# AlimentationLabo-Debutant.net
KiCad netlist of a schematic drawn in EAGLE
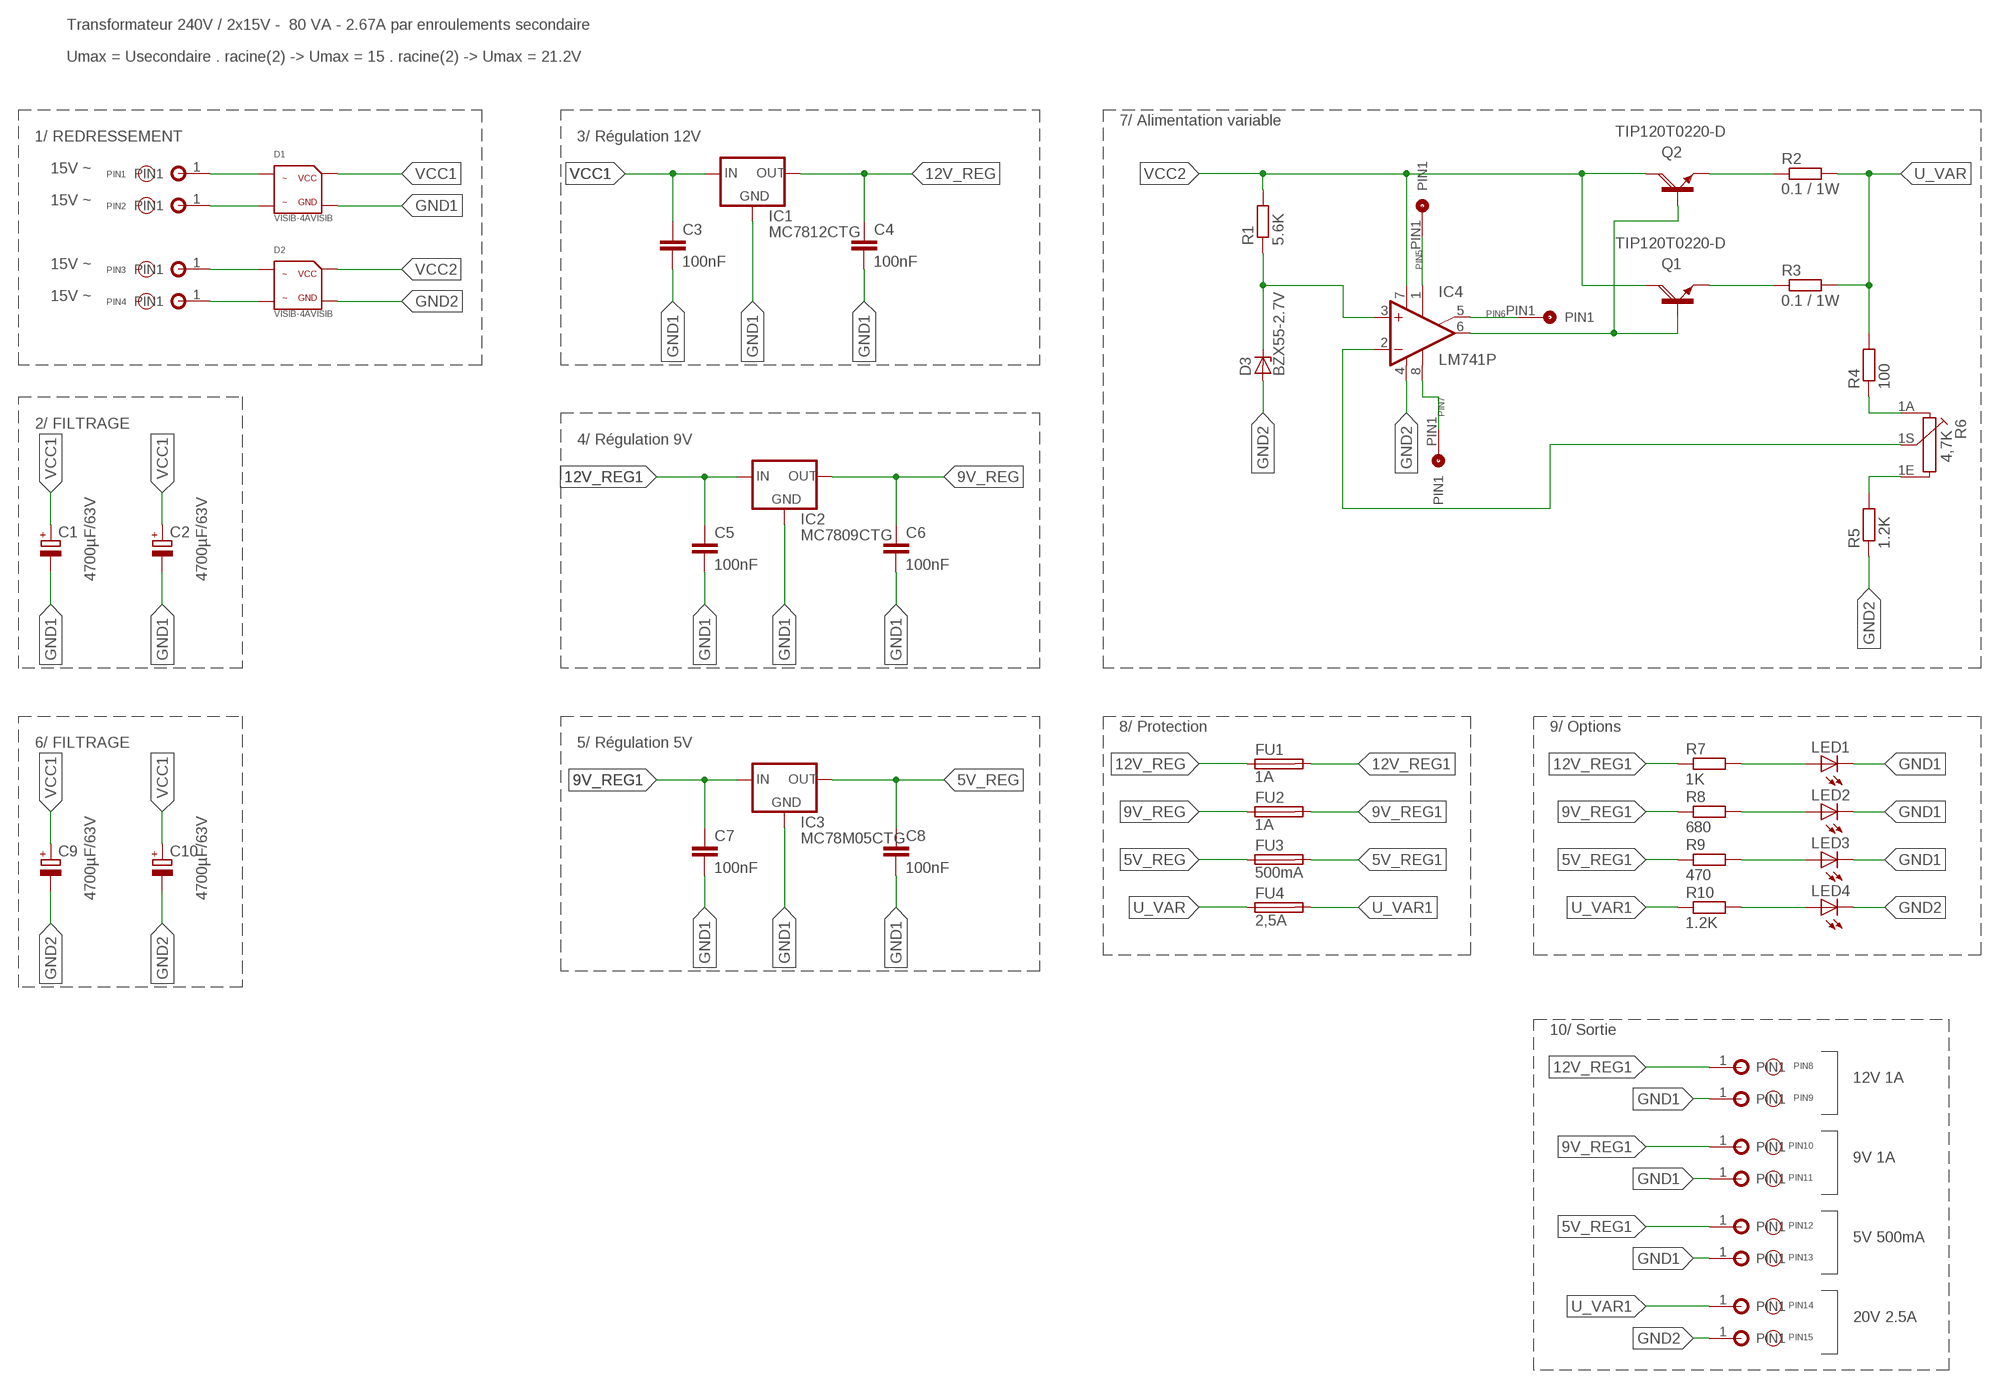
[diagram p0: schematic, sheet 1]

(export (version "E")
  (design (tool "Eeschema 10.0.6"))
  (components
    (comp (ref "C1")
      (value "4700µF/63V")
      (footprint "eagle-import:EB25D")
      (libsource (lib "eagle-import") (part "CPOL-EUE10-25"))
    )
    (comp (ref "C2")
      (value "4700µF/63V")
      (footprint "eagle-import:EB25D")
      (libsource (lib "eagle-import") (part "CPOL-EUE10-25"))
    )
    (comp (ref "C3")
      (value "100nF")
      (footprint "eagle-import:C0805")
      (libsource (lib "eagle-import") (part "C-EUC0805"))
    )
    (comp (ref "C4")
      (value "100nF")
      (footprint "eagle-import:C0805")
      (libsource (lib "eagle-import") (part "C-EUC0805"))
    )
    (comp (ref "C5")
      (value "100nF")
      (footprint "eagle-import:C0805")
      (libsource (lib "eagle-import") (part "C-EUC0805"))
    )
    (comp (ref "C6")
      (value "100nF")
      (footprint "eagle-import:C0805")
      (libsource (lib "eagle-import") (part "C-EUC0805"))
    )
    (comp (ref "C7")
      (value "100nF")
      (footprint "eagle-import:C0805")
      (libsource (lib "eagle-import") (part "C-EUC0805"))
    )
    (comp (ref "C8")
      (value "100nF")
      (footprint "eagle-import:C0805")
      (libsource (lib "eagle-import") (part "C-EUC0805"))
    )
    (comp (ref "C9")
      (value "4700µF/63V")
      (footprint "eagle-import:EB25D")
      (libsource (lib "eagle-import") (part "CPOL-EUE10-25"))
    )
    (comp (ref "C10")
      (value "4700µF/63V")
      (footprint "eagle-import:EB25D")
      (libsource (lib "eagle-import") (part "CPOL-EUE10-25"))
    )
    (comp (ref "D1")
      (value "VISIB-4AVISIB")
      (footprint "eagle-import:VISIB-4A")
      (libsource (lib "eagle-import") (part "VISIB-4AVISIB"))
    )
    (comp (ref "D2")
      (value "VISIB-4AVISIB")
      (footprint "eagle-import:VISIB-4A")
      (libsource (lib "eagle-import") (part "VISIB-4AVISIB"))
    )
    (comp (ref "D3")
      (value "BZX55-2.7V")
      (footprint "eagle-import:DO35Z10")
      (libsource (lib "eagle-import") (part "BZX55"))
    )
    (comp (ref "FU1")
      (value "1A")
      (footprint "eagle-import:MC36226")
      (libsource (lib "eagle-import") (part "MC36226SMD1812"))
    )
    (comp (ref "FU2")
      (value "1A")
      (footprint "eagle-import:MC36226")
      (libsource (lib "eagle-import") (part "MC36226SMD1812"))
    )
    (comp (ref "FU3")
      (value "500mA")
      (footprint "eagle-import:MC36226")
      (libsource (lib "eagle-import") (part "MC36226SMD1812"))
    )
    (comp (ref "FU4")
      (value "2,5A")
      (footprint "eagle-import:MC36226")
      (libsource (lib "eagle-import") (part "MC36226SMD1812"))
    )
    (comp (ref "IC1")
      (value "MC7812CTG")
      (footprint "eagle-import:78XXS")
      (libsource (lib "eagle-import") (part "78XXS"))
    )
    (comp (ref "IC2")
      (value "MC7809CTG")
      (footprint "eagle-import:78XXS")
      (libsource (lib "eagle-import") (part "78XXS"))
    )
    (comp (ref "IC3")
      (value "MC78M05CTG")
      (footprint "eagle-import:78XXS")
      (libsource (lib "eagle-import") (part "78XXS"))
    )
    (comp (ref "IC4")
      (value "LM741P")
      (footprint "eagle-import:DIL08")
      (libsource (lib "eagle-import") (part "741PLM"))
    )
    (comp (ref "LED1")
      (value "LED5MM")
      (footprint "eagle-import:LED5MM")
      (libsource (lib "eagle-import") (part "LED5MM"))
    )
    (comp (ref "LED2")
      (value "LED5MM")
      (footprint "eagle-import:LED5MM")
      (libsource (lib "eagle-import") (part "LED5MM"))
    )
    (comp (ref "LED3")
      (value "LED5MM")
      (footprint "eagle-import:LED5MM")
      (libsource (lib "eagle-import") (part "LED5MM"))
    )
    (comp (ref "LED4")
      (value "LED5MM")
      (footprint "eagle-import:LED5MM")
      (libsource (lib "eagle-import") (part "LED5MM"))
    )
    (comp (ref "PIN1")
      (value "CON-FILTRAVERSANT-1PIN")
      (footprint "eagle-import:CON-FILTRAVERSANT-T2")
      (libsource (lib "eagle-import") (part "CON-FILTRAVERSANT-1PIN"))
    )
    (comp (ref "PIN2")
      (value "CON-FILTRAVERSANT-1PIN")
      (footprint "eagle-import:CON-FILTRAVERSANT-T2")
      (libsource (lib "eagle-import") (part "CON-FILTRAVERSANT-1PIN"))
    )
    (comp (ref "PIN3")
      (value "CON-FILTRAVERSANT-1PIN")
      (footprint "eagle-import:CON-FILTRAVERSANT-T2")
      (libsource (lib "eagle-import") (part "CON-FILTRAVERSANT-1PIN"))
    )
    (comp (ref "PIN4")
      (value "CON-FILTRAVERSANT-1PIN")
      (footprint "eagle-import:CON-FILTRAVERSANT-T2")
      (libsource (lib "eagle-import") (part "CON-FILTRAVERSANT-1PIN"))
    )
    (comp (ref "PIN5")
      (value "CON-TRAV-1PIN")
      (footprint "eagle-import:CON-TRAV-1")
      (libsource (lib "eagle-import") (part "CON-TRAV-1PIN"))
    )
    (comp (ref "PIN6")
      (value "CON-TRAV-1PIN")
      (footprint "eagle-import:CON-TRAV-1")
      (libsource (lib "eagle-import") (part "CON-TRAV-1PIN"))
    )
    (comp (ref "PIN7")
      (value "CON-TRAV-1PIN")
      (footprint "eagle-import:CON-TRAV-1")
      (libsource (lib "eagle-import") (part "CON-TRAV-1PIN"))
    )
    (comp (ref "PIN8")
      (value "CON-FILTRAVERSANT-1PIN")
      (footprint "eagle-import:CON-FILTRAVERSANT-T2")
      (libsource (lib "eagle-import") (part "CON-FILTRAVERSANT-1PIN"))
    )
    (comp (ref "PIN9")
      (value "CON-FILTRAVERSANT-1PIN")
      (footprint "eagle-import:CON-FILTRAVERSANT-T2")
      (libsource (lib "eagle-import") (part "CON-FILTRAVERSANT-1PIN"))
    )
    (comp (ref "PIN10")
      (value "CON-FILTRAVERSANT-1PIN")
      (footprint "eagle-import:CON-FILTRAVERSANT-T2")
      (libsource (lib "eagle-import") (part "CON-FILTRAVERSANT-1PIN"))
    )
    (comp (ref "PIN11")
      (value "CON-FILTRAVERSANT-1PIN")
      (footprint "eagle-import:CON-FILTRAVERSANT-T2")
      (libsource (lib "eagle-import") (part "CON-FILTRAVERSANT-1PIN"))
    )
    (comp (ref "PIN12")
      (value "CON-FILTRAVERSANT-1PIN")
      (footprint "eagle-import:CON-FILTRAVERSANT-T2")
      (libsource (lib "eagle-import") (part "CON-FILTRAVERSANT-1PIN"))
    )
    (comp (ref "PIN13")
      (value "CON-FILTRAVERSANT-1PIN")
      (footprint "eagle-import:CON-FILTRAVERSANT-T2")
      (libsource (lib "eagle-import") (part "CON-FILTRAVERSANT-1PIN"))
    )
    (comp (ref "PIN14")
      (value "CON-FILTRAVERSANT-1PIN")
      (footprint "eagle-import:CON-FILTRAVERSANT-T2")
      (libsource (lib "eagle-import") (part "CON-FILTRAVERSANT-1PIN"))
    )
    (comp (ref "PIN15")
      (value "CON-FILTRAVERSANT-1PIN")
      (footprint "eagle-import:CON-FILTRAVERSANT-T2")
      (libsource (lib "eagle-import") (part "CON-FILTRAVERSANT-1PIN"))
    )
    (comp (ref "Q1")
      (value "TIP120T0220-D")
      (footprint "eagle-import:T0220-D")
      (libsource (lib "eagle-import") (part "TIP120T0220-D"))
    )
    (comp (ref "Q2")
      (value "TIP120T0220-D")
      (footprint "eagle-import:T0220-D")
      (libsource (lib "eagle-import") (part "TIP120T0220-D"))
    )
    (comp (ref "R1")
      (value "5.6K")
      (footprint "eagle-import:R0805")
      (libsource (lib "eagle-import") (part "R-EU_R0805"))
    )
    (comp (ref "R2")
      (value "0.1 / 1W")
      (footprint "eagle-import:P0817_22")
      (libsource (lib "eagle-import") (part "R-EU_0817/22"))
    )
    (comp (ref "R3")
      (value "0.1 / 1W")
      (footprint "eagle-import:P0817_22")
      (libsource (lib "eagle-import") (part "R-EU_0817/22"))
    )
    (comp (ref "R4")
      (value "100")
      (footprint "eagle-import:R0805")
      (libsource (lib "eagle-import") (part "R-EU_R0805"))
    )
    (comp (ref "R5")
      (value "1.2K")
      (footprint "eagle-import:R0805")
      (libsource (lib "eagle-import") (part "R-EU_R0805"))
    )
    (comp (ref "R6")
      (value "4,7K")
      (footprint "eagle-import:PC16S")
      (libsource (lib "eagle-import") (part "PC16S"))
    )
    (comp (ref "R7")
      (value "1K")
      (footprint "eagle-import:R0805")
      (libsource (lib "eagle-import") (part "R-EU_R0805"))
    )
    (comp (ref "R8")
      (value "680")
      (footprint "eagle-import:R0805")
      (libsource (lib "eagle-import") (part "R-EU_R0805"))
    )
    (comp (ref "R9")
      (value "470")
      (footprint "eagle-import:R0805")
      (libsource (lib "eagle-import") (part "R-EU_R0805"))
    )
    (comp (ref "R10")
      (value "1.2K")
      (footprint "eagle-import:R0805")
      (libsource (lib "eagle-import") (part "R-EU_R0805"))
    )
  )
  (nets
    (net (code "1") (name "5V_REG") (class "Default")
      (node (ref "C8") (pin "1") (pinfunction "1_1") (pintype "passive"))
      (node (ref "FU3") (pin "1") (pinfunction "1_1") (pintype "passive"))
      (node (ref "IC3") (pin "OUT") (pinfunction "OUT_OUT") (pintype "passive"))
    )
    (net (code "2") (name "5V_REG1") (class "Default")
      (node (ref "FU3") (pin "2") (pinfunction "2_2") (pintype "passive"))
      (node (ref "PIN12") (pin "1") (pinfunction "PIN1_1") (pintype "bidirectional"))
      (node (ref "R9") (pin "1") (pinfunction "1_1") (pintype "passive"))
    )
    (net (code "3") (name "9V_REG") (class "Default")
      (node (ref "C6") (pin "1") (pinfunction "1_1") (pintype "passive"))
      (node (ref "FU2") (pin "1") (pinfunction "1_1") (pintype "passive"))
      (node (ref "IC2") (pin "OUT") (pinfunction "OUT_OUT") (pintype "passive"))
    )
    (net (code "4") (name "9V_REG1") (class "Default")
      (node (ref "C7") (pin "1") (pinfunction "1_1") (pintype "passive"))
      (node (ref "FU2") (pin "2") (pinfunction "2_2") (pintype "passive"))
      (node (ref "IC3") (pin "IN") (pinfunction "IN_IN") (pintype "input"))
      (node (ref "PIN10") (pin "1") (pinfunction "PIN1_1") (pintype "bidirectional"))
      (node (ref "R8") (pin "1") (pinfunction "1_1") (pintype "passive"))
    )
    (net (code "5") (name "12V_REG") (class "Default")
      (node (ref "C4") (pin "1") (pinfunction "1_1") (pintype "passive"))
      (node (ref "FU1") (pin "1") (pinfunction "1_1") (pintype "passive"))
      (node (ref "IC1") (pin "OUT") (pinfunction "OUT_OUT") (pintype "passive"))
    )
    (net (code "6") (name "12V_REG1") (class "Default")
      (node (ref "C5") (pin "1") (pinfunction "1_1") (pintype "passive"))
      (node (ref "FU1") (pin "2") (pinfunction "2_2") (pintype "passive"))
      (node (ref "IC2") (pin "IN") (pinfunction "IN_IN") (pintype "input"))
      (node (ref "PIN8") (pin "1") (pinfunction "PIN1_1") (pintype "bidirectional"))
      (node (ref "R7") (pin "1") (pinfunction "1_1") (pintype "passive"))
    )
    (net (code "7") (name "GND1") (class "Default")
      (node (ref "C1") (pin "-") (pinfunction "-_-") (pintype "passive"))
      (node (ref "C2") (pin "-") (pinfunction "-_-") (pintype "passive"))
      (node (ref "C3") (pin "2") (pinfunction "2_2") (pintype "passive"))
      (node (ref "C4") (pin "2") (pinfunction "2_2") (pintype "passive"))
      (node (ref "C5") (pin "2") (pinfunction "2_2") (pintype "passive"))
      (node (ref "C6") (pin "2") (pinfunction "2_2") (pintype "passive"))
      (node (ref "C7") (pin "2") (pinfunction "2_2") (pintype "passive"))
      (node (ref "C8") (pin "2") (pinfunction "2_2") (pintype "passive"))
      (node (ref "D1") (pin "GND") (pinfunction "GND_GND") (pintype "bidirectional"))
      (node (ref "IC1") (pin "GND") (pinfunction "GND_GND") (pintype "input"))
      (node (ref "IC2") (pin "GND") (pinfunction "GND_GND") (pintype "input"))
      (node (ref "IC3") (pin "GND") (pinfunction "GND_GND") (pintype "input"))
      (node (ref "LED1") (pin "K") (pinfunction "C_K") (pintype "passive"))
      (node (ref "LED2") (pin "K") (pinfunction "C_K") (pintype "passive"))
      (node (ref "LED3") (pin "K") (pinfunction "C_K") (pintype "passive"))
      (node (ref "PIN11") (pin "1") (pinfunction "PIN1_1") (pintype "bidirectional"))
      (node (ref "PIN13") (pin "1") (pinfunction "PIN1_1") (pintype "bidirectional"))
      (node (ref "PIN9") (pin "1") (pinfunction "PIN1_1") (pintype "bidirectional"))
    )
    (net (code "8") (name "GND2") (class "Default")
      (node (ref "C10") (pin "-") (pinfunction "-_-") (pintype "passive"))
      (node (ref "C9") (pin "-") (pinfunction "-_-") (pintype "passive"))
      (node (ref "D2") (pin "GND") (pinfunction "GND_GND") (pintype "bidirectional"))
      (node (ref "D3") (pin "A") (pinfunction "A_A") (pintype "passive"))
      (node (ref "IC4") (pin "4") (pinfunction "V-_4") (pintype "power_in"))
      (node (ref "LED4") (pin "K") (pinfunction "C_K") (pintype "passive"))
      (node (ref "PIN15") (pin "1") (pinfunction "PIN1_1") (pintype "bidirectional"))
      (node (ref "R5") (pin "1") (pinfunction "1_1") (pintype "passive"))
    )
    (net (code "9") (name "Net-(IC4-+IN)") (class "Default")
      (node (ref "D3") (pin "C") (pinfunction "C_C") (pintype "passive"))
      (node (ref "IC4") (pin "3") (pinfunction "+IN_3") (pintype "input"))
      (node (ref "R1") (pin "1") (pinfunction "1_1") (pintype "passive"))
    )
    (net (code "10") (name "Net-(IC4--IN)") (class "Default")
      (node (ref "IC4") (pin "2") (pinfunction "-IN_2") (pintype "input"))
      (node (ref "R6") (pin "1S") (pinfunction "1S_1S") (pintype "passive"))
    )
    (net (code "11") (name "Net-(IC4-ON1)") (class "Default")
      (node (ref "IC4") (pin "1") (pinfunction "ON1_1") (pintype "passive"))
      (node (ref "PIN5") (pin "PIN1") (pinfunction "PIN1_PIN1") (pintype "bidirectional"))
    )
    (net (code "12") (name "Net-(IC4-ON2)") (class "Default")
      (node (ref "IC4") (pin "5") (pinfunction "ON2_5") (pintype "passive"))
      (node (ref "PIN6") (pin "PIN1") (pinfunction "PIN1_PIN1") (pintype "bidirectional"))
    )
    (net (code "13") (name "Net-(IC4-OPT)") (class "Default")
      (node (ref "IC4") (pin "8") (pinfunction "OPT_8") (pintype "passive"))
      (node (ref "PIN7") (pin "PIN1") (pinfunction "PIN1_PIN1") (pintype "bidirectional"))
    )
    (net (code "14") (name "Net-(IC4-OUT)") (class "Default")
      (node (ref "IC4") (pin "6") (pinfunction "OUT_6") (pintype "output"))
      (node (ref "Q1") (pin "B") (pinfunction "B_B") (pintype "passive"))
      (node (ref "Q2") (pin "B") (pinfunction "B_B") (pintype "passive"))
    )
    (net (code "15") (name "Net-(LED1-PadA)") (class "Default")
      (node (ref "LED1") (pin "A") (pinfunction "A_A") (pintype "passive"))
      (node (ref "R7") (pin "2") (pinfunction "2_2") (pintype "passive"))
    )
    (net (code "16") (name "Net-(LED2-PadA)") (class "Default")
      (node (ref "LED2") (pin "A") (pinfunction "A_A") (pintype "passive"))
      (node (ref "R8") (pin "2") (pinfunction "2_2") (pintype "passive"))
    )
    (net (code "17") (name "Net-(LED3-PadA)") (class "Default")
      (node (ref "LED3") (pin "A") (pinfunction "A_A") (pintype "passive"))
      (node (ref "R9") (pin "2") (pinfunction "2_2") (pintype "passive"))
    )
    (net (code "18") (name "Net-(LED4-PadA)") (class "Default")
      (node (ref "LED4") (pin "A") (pinfunction "A_A") (pintype "passive"))
      (node (ref "R10") (pin "2") (pinfunction "2_2") (pintype "passive"))
    )
    (net (code "19") (name "Net-(PIN1-PIN1)") (class "Default")
      (node (ref "D1") (pin "ALT1") (pinfunction "ALT1_ALT1") (pintype "bidirectional"))
      (node (ref "PIN1") (pin "1") (pinfunction "PIN1_1") (pintype "bidirectional"))
    )
    (net (code "20") (name "Net-(PIN2-PIN1)") (class "Default")
      (node (ref "D1") (pin "ALT2") (pinfunction "ALT2_ALT2") (pintype "bidirectional"))
      (node (ref "PIN2") (pin "1") (pinfunction "PIN1_1") (pintype "bidirectional"))
    )
    (net (code "21") (name "Net-(PIN3-PIN1)") (class "Default")
      (node (ref "D2") (pin "ALT1") (pinfunction "ALT1_ALT1") (pintype "bidirectional"))
      (node (ref "PIN3") (pin "1") (pinfunction "PIN1_1") (pintype "bidirectional"))
    )
    (net (code "22") (name "Net-(PIN4-PIN1)") (class "Default")
      (node (ref "D2") (pin "ALT2") (pinfunction "ALT2_ALT2") (pintype "bidirectional"))
      (node (ref "PIN4") (pin "1") (pinfunction "PIN1_1") (pintype "bidirectional"))
    )
    (net (code "23") (name "Net-(Q1-PadE)") (class "Default")
      (node (ref "Q1") (pin "E") (pinfunction "E_E") (pintype "passive"))
      (node (ref "R3") (pin "1") (pinfunction "1_1") (pintype "passive"))
    )
    (net (code "24") (name "Net-(Q2-PadE)") (class "Default")
      (node (ref "Q2") (pin "E") (pinfunction "E_E") (pintype "passive"))
      (node (ref "R2") (pin "1") (pinfunction "1_1") (pintype "passive"))
    )
    (net (code "25") (name "Net-(R4-Pad1)") (class "Default")
      (node (ref "R4") (pin "1") (pinfunction "1_1") (pintype "passive"))
      (node (ref "R6") (pin "1A") (pinfunction "1A_1A") (pintype "passive"))
    )
    (net (code "26") (name "Net-(R5-Pad2)") (class "Default")
      (node (ref "R5") (pin "2") (pinfunction "2_2") (pintype "passive"))
      (node (ref "R6") (pin "1E") (pinfunction "1E_1E") (pintype "passive"))
    )
    (net (code "27") (name "U_VAR") (class "Default")
      (node (ref "FU4") (pin "1") (pinfunction "1_1") (pintype "passive"))
      (node (ref "R2") (pin "2") (pinfunction "2_2") (pintype "passive"))
      (node (ref "R3") (pin "2") (pinfunction "2_2") (pintype "passive"))
      (node (ref "R4") (pin "2") (pinfunction "2_2") (pintype "passive"))
    )
    (net (code "28") (name "U_VAR1") (class "Default")
      (node (ref "FU4") (pin "2") (pinfunction "2_2") (pintype "passive"))
      (node (ref "PIN14") (pin "1") (pinfunction "PIN1_1") (pintype "bidirectional"))
      (node (ref "R10") (pin "1") (pinfunction "1_1") (pintype "passive"))
    )
    (net (code "29") (name "VCC1") (class "Default")
      (node (ref "C1") (pin "+") (pinfunction "+_+") (pintype "passive"))
      (node (ref "C10") (pin "+") (pinfunction "+_+") (pintype "passive"))
      (node (ref "C2") (pin "+") (pinfunction "+_+") (pintype "passive"))
      (node (ref "C3") (pin "1") (pinfunction "1_1") (pintype "passive"))
      (node (ref "C9") (pin "+") (pinfunction "+_+") (pintype "passive"))
      (node (ref "D1") (pin "VCC") (pinfunction "VCC_VCC") (pintype "bidirectional"))
      (node (ref "IC1") (pin "IN") (pinfunction "IN_IN") (pintype "input"))
    )
    (net (code "30") (name "VCC2") (class "Default")
      (node (ref "D2") (pin "VCC") (pinfunction "VCC_VCC") (pintype "bidirectional"))
      (node (ref "IC4") (pin "7") (pinfunction "V+_7") (pintype "power_in"))
      (node (ref "Q1") (pin "C") (pinfunction "C_C") (pintype "passive"))
      (node (ref "Q2") (pin "C") (pinfunction "C_C") (pintype "passive"))
      (node (ref "R1") (pin "2") (pinfunction "2_2") (pintype "passive"))
    )
  )
)
